# control1.net
KiCad netlist of a schematic drawn in EAGLE
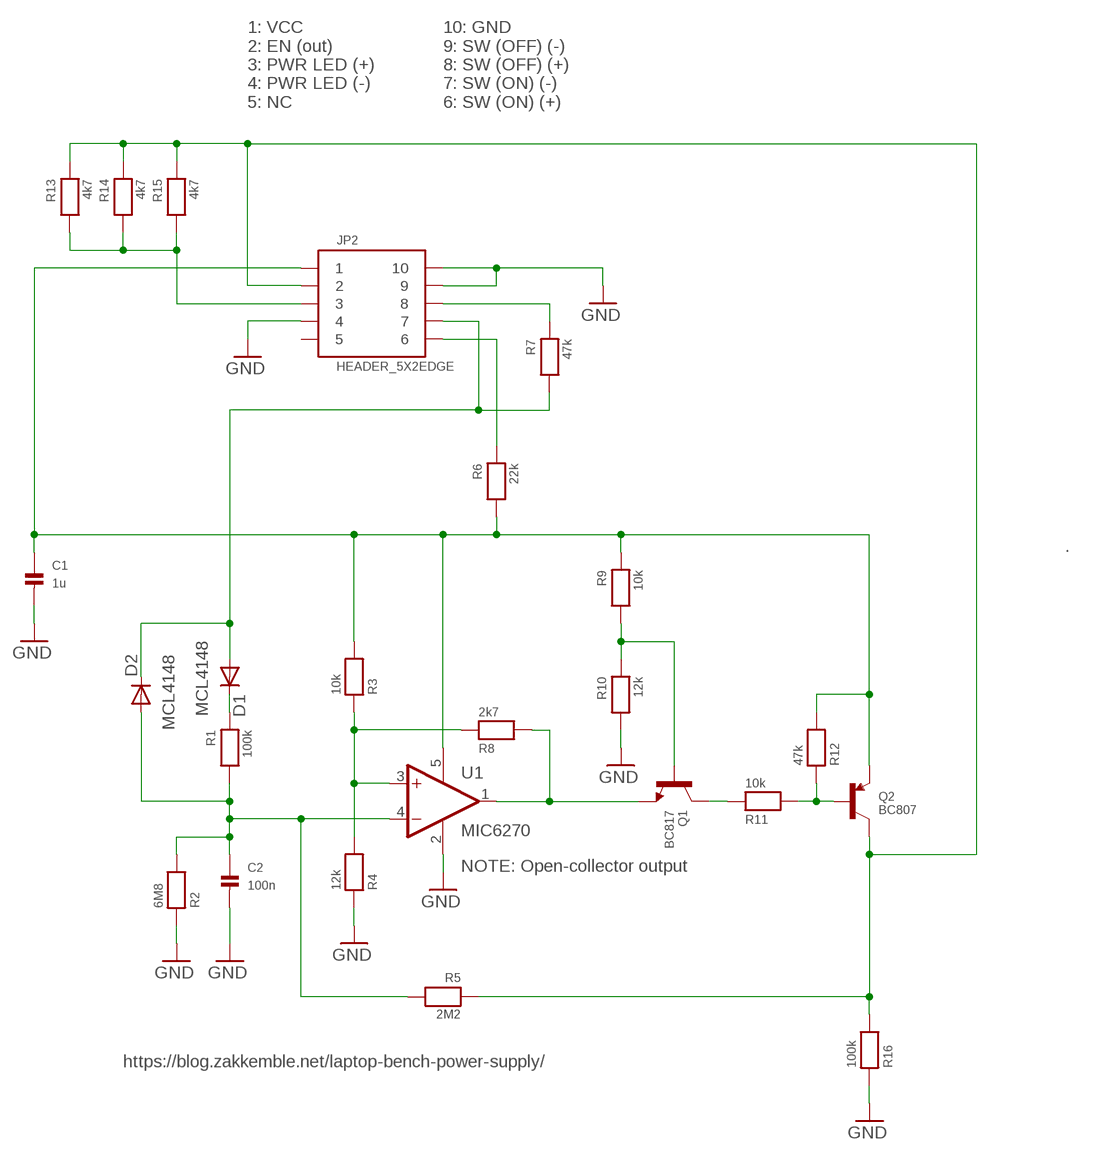
[diagram p0: schematic, sheet 1]

(export (version "E")
  (design (tool "Eeschema 10.0.6"))
  (components
    (comp (ref "C1")
      (value "1u")
      (footprint "eagle-import:0402")
      (libsource (lib "eagle-import") (part "zak_CAP_CERAMIC0402"))
    )
    (comp (ref "C2")
      (value "100n")
      (footprint "eagle-import:_0603MP")
      (libsource (lib "eagle-import") (part "CAP_CERAMIC_0603MP"))
    )
    (comp (ref "D1")
      (value "MCL4148")
      (footprint "eagle-import:MICROMELF-R")
      (libsource (lib "eagle-import") (part "DIODE-MICROMELF-R"))
    )
    (comp (ref "D2")
      (value "MCL4148")
      (footprint "eagle-import:MICROMELF-R")
      (libsource (lib "eagle-import") (part "DIODE-MICROMELF-R"))
    )
    (comp (ref "JP2")
      (value "HEADER_5X2EDGE")
      (footprint "eagle-import:HEADER_EDGE_5X2")
      (libsource (lib "eagle-import") (part "HEADER_5X2EDGE"))
    )
    (comp (ref "Q1")
      (value "BC817")
      (footprint "eagle-import:SOT23-WIDE")
      (libsource (lib "eagle-import") (part "TRANSISTOR_NPNWIDE"))
    )
    (comp (ref "Q2")
      (value "BC807")
      (footprint "eagle-import:SOT23-WIDE")
      (libsource (lib "eagle-import") (part "TRANSISTOR_PNPWIDE"))
    )
    (comp (ref "R1")
      (value "100k")
      (footprint "eagle-import:0402")
      (libsource (lib "eagle-import") (part "RESISTOR0402"))
    )
    (comp (ref "R2")
      (value "6M8")
      (footprint "eagle-import:0402")
      (libsource (lib "eagle-import") (part "RESISTOR0402"))
    )
    (comp (ref "R3")
      (value "10k")
      (footprint "eagle-import:0402")
      (libsource (lib "eagle-import") (part "RESISTOR0402"))
    )
    (comp (ref "R4")
      (value "12k")
      (footprint "eagle-import:0402")
      (libsource (lib "eagle-import") (part "RESISTOR0402"))
    )
    (comp (ref "R5")
      (value "2M2")
      (footprint "eagle-import:0402")
      (libsource (lib "eagle-import") (part "RESISTOR0402"))
    )
    (comp (ref "R6")
      (value "22k")
      (footprint "eagle-import:0402")
      (libsource (lib "eagle-import") (part "RESISTOR0402"))
    )
    (comp (ref "R7")
      (value "47k")
      (footprint "eagle-import:0402")
      (libsource (lib "eagle-import") (part "RESISTOR0402"))
    )
    (comp (ref "R8")
      (value "2k7")
      (footprint "eagle-import:0402")
      (libsource (lib "eagle-import") (part "RESISTOR0402"))
    )
    (comp (ref "R9")
      (value "10k")
      (footprint "eagle-import:0402")
      (libsource (lib "eagle-import") (part "RESISTOR0402"))
    )
    (comp (ref "R10")
      (value "12k")
      (footprint "eagle-import:0402")
      (libsource (lib "eagle-import") (part "RESISTOR0402"))
    )
    (comp (ref "R11")
      (value "10k")
      (footprint "eagle-import:0402")
      (libsource (lib "eagle-import") (part "RESISTOR0402"))
    )
    (comp (ref "R12")
      (value "47k")
      (footprint "eagle-import:0402")
      (libsource (lib "eagle-import") (part "RESISTOR0402"))
    )
    (comp (ref "R13")
      (value "4k7")
      (footprint "eagle-import:0402")
      (libsource (lib "eagle-import") (part "RESISTOR0402"))
    )
    (comp (ref "R14")
      (value "4k7")
      (footprint "eagle-import:0402")
      (libsource (lib "eagle-import") (part "RESISTOR0402"))
    )
    (comp (ref "R15")
      (value "4k7")
      (footprint "eagle-import:0402")
      (libsource (lib "eagle-import") (part "RESISTOR0402"))
    )
    (comp (ref "R16")
      (value "100k")
      (footprint "eagle-import:0402")
      (libsource (lib "eagle-import") (part "RESISTOR0402"))
    )
    (comp (ref "U1")
      (value "MIC6270")
      (footprint "eagle-import:SOT95P275X110-5N")
      (libsource (lib "eagle-import") (part "MIC6270"))
    )
  )
  (nets
    (net (code "1") (name "GND") (class "Default")
      (node (ref "C1") (pin "2") (pinfunction "P$2_2") (pintype "passive"))
      (node (ref "C2") (pin "2") (pinfunction "P$2_2") (pintype "passive"))
      (node (ref "JP2") (pin "10") (pinfunction "10_10") (pintype "passive"))
      (node (ref "JP2") (pin "4") (pinfunction "4_4") (pintype "passive"))
      (node (ref "JP2") (pin "9") (pinfunction "9_9") (pintype "passive"))
      (node (ref "R10") (pin "2") (pinfunction "2_2") (pintype "passive"))
      (node (ref "R16") (pin "1") (pinfunction "1_1") (pintype "passive"))
      (node (ref "R2") (pin "1") (pinfunction "1_1") (pintype "passive"))
      (node (ref "R4") (pin "1") (pinfunction "1_1") (pintype "passive"))
      (node (ref "U1") (pin "2") (pinfunction "GND_2") (pintype "power_in"))
    )
    (net (code "2") (name "Net-(C1-P$1)") (class "Default")
      (node (ref "C1") (pin "1") (pinfunction "P$1_1") (pintype "passive"))
      (node (ref "JP2") (pin "1") (pinfunction "1_1") (pintype "passive"))
      (node (ref "Q2") (pin "2") (pinfunction "E_2") (pintype "passive"))
      (node (ref "R12") (pin "2") (pinfunction "2_2") (pintype "passive"))
      (node (ref "R3") (pin "2") (pinfunction "2_2") (pintype "passive"))
      (node (ref "R6") (pin "2") (pinfunction "2_2") (pintype "passive"))
      (node (ref "R9") (pin "1") (pinfunction "1_1") (pintype "passive"))
      (node (ref "U1") (pin "5") (pinfunction "V+_5") (pintype "power_in"))
    )
    (net (code "3") (name "Net-(C2-P$1)") (class "Default")
      (node (ref "C2") (pin "1") (pinfunction "P$1_1") (pintype "passive"))
      (node (ref "D2") (pin "A") (pinfunction "A_A") (pintype "passive"))
      (node (ref "R1") (pin "2") (pinfunction "2_2") (pintype "passive"))
      (node (ref "R2") (pin "2") (pinfunction "2_2") (pintype "passive"))
      (node (ref "R5") (pin "2") (pinfunction "2_2") (pintype "passive"))
      (node (ref "U1") (pin "4") (pinfunction "-IN_4") (pintype "input"))
    )
    (net (code "4") (name "Net-(D1-PadA)") (class "Default")
      (node (ref "D1") (pin "A") (pinfunction "A_A") (pintype "passive"))
      (node (ref "D2") (pin "C") (pinfunction "C_C") (pintype "passive"))
      (node (ref "JP2") (pin "7") (pinfunction "7_7") (pintype "passive"))
      (node (ref "R7") (pin "2") (pinfunction "2_2") (pintype "passive"))
    )
    (net (code "5") (name "Net-(D1-PadC)") (class "Default")
      (node (ref "D1") (pin "C") (pinfunction "C_C") (pintype "passive"))
      (node (ref "R1") (pin "1") (pinfunction "1_1") (pintype "passive"))
    )
    (net (code "6") (name "Net-(JP2-Pad3)") (class "Default")
      (node (ref "JP2") (pin "3") (pinfunction "3_3") (pintype "passive"))
      (node (ref "R13") (pin "2") (pinfunction "2_2") (pintype "passive"))
      (node (ref "R14") (pin "2") (pinfunction "2_2") (pintype "passive"))
      (node (ref "R15") (pin "2") (pinfunction "2_2") (pintype "passive"))
    )
    (net (code "7") (name "Net-(JP2-Pad6)") (class "Default")
      (node (ref "JP2") (pin "6") (pinfunction "6_6") (pintype "passive"))
      (node (ref "R6") (pin "1") (pinfunction "1_1") (pintype "passive"))
    )
    (net (code "8") (name "Net-(JP2-Pad8)") (class "Default")
      (node (ref "JP2") (pin "8") (pinfunction "8_8") (pintype "passive"))
      (node (ref "R7") (pin "1") (pinfunction "1_1") (pintype "passive"))
    )
    (net (code "9") (name "Net-(Q1-B)") (class "Default")
      (node (ref "Q1") (pin "1") (pinfunction "B_1") (pintype "passive"))
      (node (ref "R10") (pin "1") (pinfunction "1_1") (pintype "passive"))
      (node (ref "R9") (pin "2") (pinfunction "2_2") (pintype "passive"))
    )
    (net (code "10") (name "Net-(Q1-C)") (class "Default")
      (node (ref "Q1") (pin "3") (pinfunction "C_3") (pintype "passive"))
      (node (ref "R11") (pin "1") (pinfunction "1_1") (pintype "passive"))
    )
    (net (code "11") (name "Net-(Q1-E)") (class "Default")
      (node (ref "Q1") (pin "2") (pinfunction "E_2") (pintype "passive"))
      (node (ref "R8") (pin "2") (pinfunction "2_2") (pintype "passive"))
      (node (ref "U1") (pin "1") (pinfunction "OUT_1") (pintype "output"))
    )
    (net (code "12") (name "Net-(Q2-B)") (class "Default")
      (node (ref "Q2") (pin "1") (pinfunction "B_1") (pintype "passive"))
      (node (ref "R11") (pin "2") (pinfunction "2_2") (pintype "passive"))
      (node (ref "R12") (pin "1") (pinfunction "1_1") (pintype "passive"))
    )
    (net (code "13") (name "Net-(Q2-C)") (class "Default")
      (node (ref "JP2") (pin "2") (pinfunction "2_2") (pintype "passive"))
      (node (ref "Q2") (pin "3") (pinfunction "C_3") (pintype "passive"))
      (node (ref "R13") (pin "1") (pinfunction "1_1") (pintype "passive"))
      (node (ref "R14") (pin "1") (pinfunction "1_1") (pintype "passive"))
      (node (ref "R15") (pin "1") (pinfunction "1_1") (pintype "passive"))
      (node (ref "R16") (pin "2") (pinfunction "2_2") (pintype "passive"))
      (node (ref "R5") (pin "1") (pinfunction "1_1") (pintype "passive"))
    )
    (net (code "14") (name "Net-(U1-+IN)") (class "Default")
      (node (ref "R3") (pin "1") (pinfunction "1_1") (pintype "passive"))
      (node (ref "R4") (pin "2") (pinfunction "2_2") (pintype "passive"))
      (node (ref "R8") (pin "1") (pinfunction "1_1") (pintype "passive"))
      (node (ref "U1") (pin "3") (pinfunction "+IN_3") (pintype "input"))
    )
    (net (code "15") (name "unconnected-(JP2-Pad5)") (class "Default")
      (node (ref "JP2") (pin "5") (pinfunction "5_5") (pintype "passive"))
    )
  )
)
